# Sheet4.net
KiCad netlist of a schematic drawn in Altium Designer
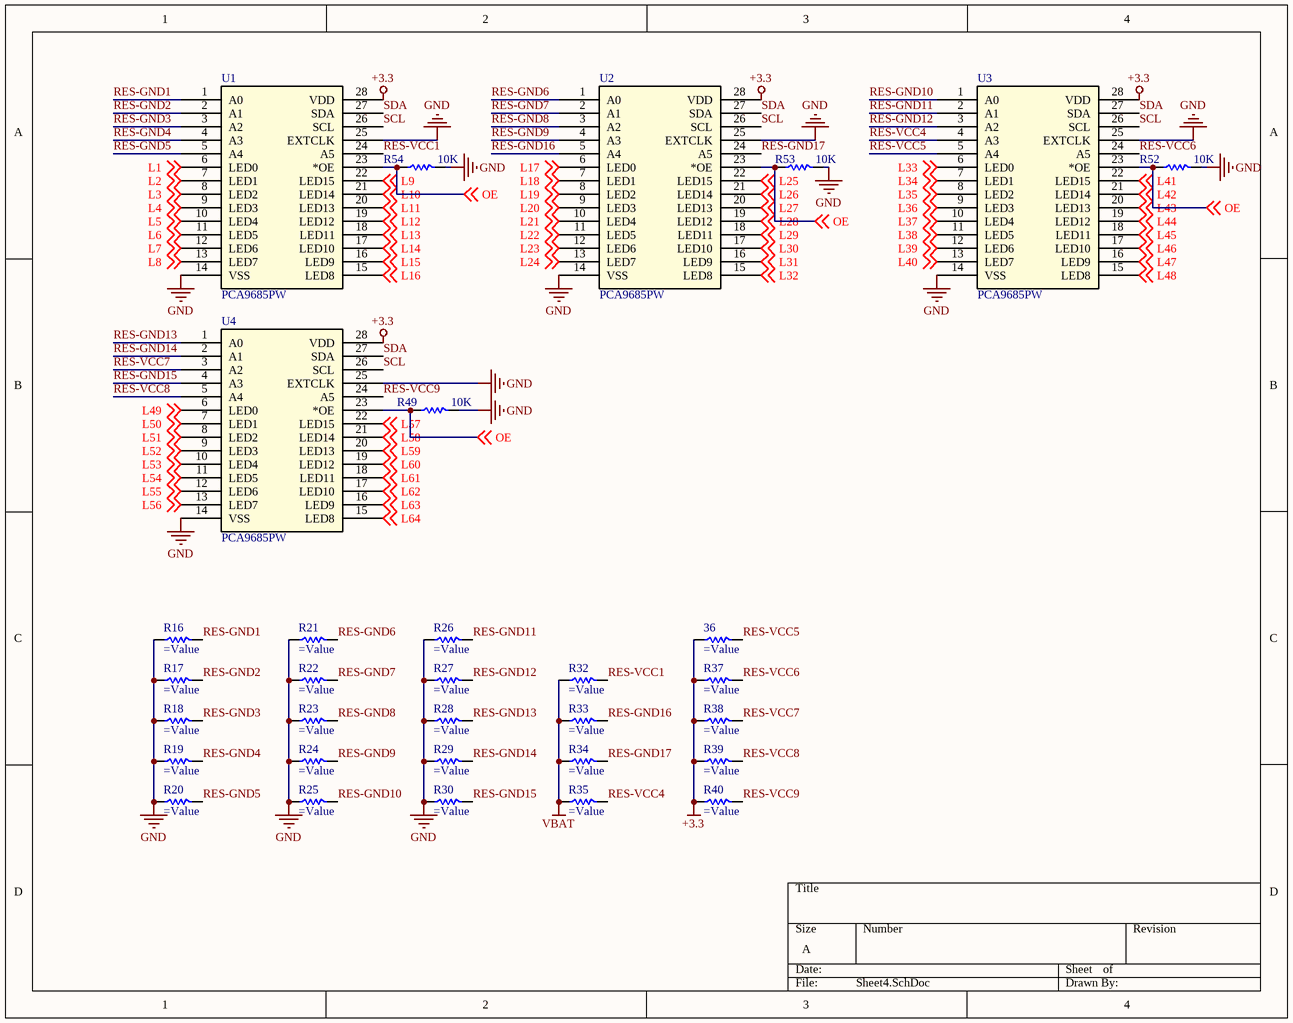
[diagram p0: Sheet4.SchDoc]

(export (version "E")
  (design (tool "Eeschema 10.0.6"))
  (components
    (comp (ref "36")
      (value "~")
      (footprint "R 0805")
      (description "Chip resistor")
      (fields (field (name "版权归属") "源创客"))
      (libsource (lib "Passive (Resistor-Capacitor-Inductor-Veristor-Ferrite)") (part "R"))
    )
    (comp (ref "R16")
      (value "~")
      (footprint "R 0805")
      (description "Chip resistor")
      (fields (field (name "版权归属") "源创客"))
      (libsource (lib "Passive (Resistor-Capacitor-Inductor-Veristor-Ferrite)") (part "R"))
    )
    (comp (ref "R17")
      (value "~")
      (footprint "R 0805")
      (description "Chip resistor")
      (fields (field (name "版权归属") "源创客"))
      (libsource (lib "Passive (Resistor-Capacitor-Inductor-Veristor-Ferrite)") (part "R"))
    )
    (comp (ref "R18")
      (value "~")
      (footprint "R 0805")
      (description "Chip resistor")
      (fields (field (name "版权归属") "源创客"))
      (libsource (lib "Passive (Resistor-Capacitor-Inductor-Veristor-Ferrite)") (part "R"))
    )
    (comp (ref "R19")
      (value "~")
      (footprint "R 0805")
      (description "Chip resistor")
      (fields (field (name "版权归属") "源创客"))
      (libsource (lib "Passive (Resistor-Capacitor-Inductor-Veristor-Ferrite)") (part "R"))
    )
    (comp (ref "R20")
      (value "~")
      (footprint "R 0805")
      (description "Chip resistor")
      (fields (field (name "版权归属") "源创客"))
      (libsource (lib "Passive (Resistor-Capacitor-Inductor-Veristor-Ferrite)") (part "R"))
    )
    (comp (ref "R21")
      (value "~")
      (footprint "R 0805")
      (description "Chip resistor")
      (fields (field (name "版权归属") "源创客"))
      (libsource (lib "Passive (Resistor-Capacitor-Inductor-Veristor-Ferrite)") (part "R"))
    )
    (comp (ref "R22")
      (value "~")
      (footprint "R 0805")
      (description "Chip resistor")
      (fields (field (name "版权归属") "源创客"))
      (libsource (lib "Passive (Resistor-Capacitor-Inductor-Veristor-Ferrite)") (part "R"))
    )
    (comp (ref "R23")
      (value "~")
      (footprint "R 0805")
      (description "Chip resistor")
      (fields (field (name "版权归属") "源创客"))
      (libsource (lib "Passive (Resistor-Capacitor-Inductor-Veristor-Ferrite)") (part "R"))
    )
    (comp (ref "R24")
      (value "~")
      (footprint "R 0805")
      (description "Chip resistor")
      (fields (field (name "版权归属") "源创客"))
      (libsource (lib "Passive (Resistor-Capacitor-Inductor-Veristor-Ferrite)") (part "R"))
    )
    (comp (ref "R25")
      (value "~")
      (footprint "R 0805")
      (description "Chip resistor")
      (fields (field (name "版权归属") "源创客"))
      (libsource (lib "Passive (Resistor-Capacitor-Inductor-Veristor-Ferrite)") (part "R"))
    )
    (comp (ref "R26")
      (value "~")
      (footprint "R 0805")
      (description "Chip resistor")
      (fields (field (name "版权归属") "源创客"))
      (libsource (lib "Passive (Resistor-Capacitor-Inductor-Veristor-Ferrite)") (part "R"))
    )
    (comp (ref "R27")
      (value "~")
      (footprint "R 0805")
      (description "Chip resistor")
      (fields (field (name "版权归属") "源创客"))
      (libsource (lib "Passive (Resistor-Capacitor-Inductor-Veristor-Ferrite)") (part "R"))
    )
    (comp (ref "R28")
      (value "~")
      (footprint "R 0805")
      (description "Chip resistor")
      (fields (field (name "版权归属") "源创客"))
      (libsource (lib "Passive (Resistor-Capacitor-Inductor-Veristor-Ferrite)") (part "R"))
    )
    (comp (ref "R29")
      (value "~")
      (footprint "R 0805")
      (description "Chip resistor")
      (fields (field (name "版权归属") "源创客"))
      (libsource (lib "Passive (Resistor-Capacitor-Inductor-Veristor-Ferrite)") (part "R"))
    )
    (comp (ref "R30")
      (value "~")
      (footprint "R 0805")
      (description "Chip resistor")
      (fields (field (name "版权归属") "源创客"))
      (libsource (lib "Passive (Resistor-Capacitor-Inductor-Veristor-Ferrite)") (part "R"))
    )
    (comp (ref "R32")
      (value "~")
      (footprint "R 0805")
      (description "Chip resistor")
      (fields (field (name "版权归属") "源创客"))
      (libsource (lib "Passive (Resistor-Capacitor-Inductor-Veristor-Ferrite)") (part "R"))
    )
    (comp (ref "R33")
      (value "~")
      (footprint "R 0805")
      (description "Chip resistor")
      (fields (field (name "版权归属") "源创客"))
      (libsource (lib "Passive (Resistor-Capacitor-Inductor-Veristor-Ferrite)") (part "R"))
    )
    (comp (ref "R34")
      (value "~")
      (footprint "R 0805")
      (description "Chip resistor")
      (fields (field (name "版权归属") "源创客"))
      (libsource (lib "Passive (Resistor-Capacitor-Inductor-Veristor-Ferrite)") (part "R"))
    )
    (comp (ref "R35")
      (value "~")
      (footprint "R 0805")
      (description "Chip resistor")
      (fields (field (name "版权归属") "源创客"))
      (libsource (lib "Passive (Resistor-Capacitor-Inductor-Veristor-Ferrite)") (part "R"))
    )
    (comp (ref "R37")
      (value "~")
      (footprint "R 0805")
      (description "Chip resistor")
      (fields (field (name "版权归属") "源创客"))
      (libsource (lib "Passive (Resistor-Capacitor-Inductor-Veristor-Ferrite)") (part "R"))
    )
    (comp (ref "R38")
      (value "~")
      (footprint "R 0805")
      (description "Chip resistor")
      (fields (field (name "版权归属") "源创客"))
      (libsource (lib "Passive (Resistor-Capacitor-Inductor-Veristor-Ferrite)") (part "R"))
    )
    (comp (ref "R39")
      (value "~")
      (footprint "R 0805")
      (description "Chip resistor")
      (fields (field (name "版权归属") "源创客"))
      (libsource (lib "Passive (Resistor-Capacitor-Inductor-Veristor-Ferrite)") (part "R"))
    )
    (comp (ref "R40")
      (value "~")
      (footprint "R 0805")
      (description "Chip resistor")
      (fields (field (name "版权归属") "源创客"))
      (libsource (lib "Passive (Resistor-Capacitor-Inductor-Veristor-Ferrite)") (part "R"))
    )
    (comp (ref "R49")
      (value "10K")
      (footprint "R 0805")
      (description "Chip resistor")
      (fields (field (name "版权归属") "源创客"))
      (libsource (lib "Passive (Resistor-Capacitor-Inductor-Veristor-Ferrite)") (part "R"))
    )
    (comp (ref "R52")
      (value "10K")
      (footprint "R 0805")
      (description "Chip resistor")
      (fields (field (name "版权归属") "源创客"))
      (libsource (lib "Passive (Resistor-Capacitor-Inductor-Veristor-Ferrite)") (part "R"))
    )
    (comp (ref "R53")
      (value "10K")
      (footprint "R 0805")
      (description "Chip resistor")
      (fields (field (name "版权归属") "源创客"))
      (libsource (lib "Passive (Resistor-Capacitor-Inductor-Veristor-Ferrite)") (part "R"))
    )
    (comp (ref "R54")
      (value "10K")
      (footprint "R 0805")
      (description "Chip resistor")
      (fields (field (name "版权归属") "源创客"))
      (libsource (lib "Passive (Resistor-Capacitor-Inductor-Veristor-Ferrite)") (part "R"))
    )
    (comp (ref "U1")
      (value "PCA9685PW")
      (footprint "SOT361-1_NXP")
      (description "No Description Available")
      (fields (field (name "COPYRIGHT") "Copyright (C) 2018 Accelerated Designs. All rights reserved"))
      (libsource (lib "PCA9685") (part "PCA9685PW"))
    )
    (comp (ref "U2")
      (value "PCA9685PW")
      (footprint "SOT361-1_NXP")
      (description "No Description Available")
      (fields (field (name "COPYRIGHT") "Copyright (C) 2018 Accelerated Designs. All rights reserved"))
      (libsource (lib "PCA9685") (part "PCA9685PW"))
    )
    (comp (ref "U3")
      (value "PCA9685PW")
      (footprint "SOT361-1_NXP")
      (description "No Description Available")
      (fields (field (name "COPYRIGHT") "Copyright (C) 2018 Accelerated Designs. All rights reserved"))
      (libsource (lib "PCA9685") (part "PCA9685PW"))
    )
    (comp (ref "U4")
      (value "PCA9685PW")
      (footprint "SOT361-1_NXP")
      (description "No Description Available")
      (fields (field (name "COPYRIGHT") "Copyright (C) 2018 Accelerated Designs. All rights reserved"))
      (libsource (lib "PCA9685") (part "PCA9685PW"))
    )
  )
  (nets
    (net (code "1") (name "+3.3") (class "Default")
      (node (ref "36") (pin "1") (pinfunction "1_1") (pintype "passive"))
      (node (ref "R37") (pin "1") (pinfunction "1_1") (pintype "passive"))
      (node (ref "R38") (pin "1") (pinfunction "1_1") (pintype "passive"))
      (node (ref "R39") (pin "1") (pinfunction "1_1") (pintype "passive"))
      (node (ref "R40") (pin "1") (pinfunction "1_1") (pintype "passive"))
      (node (ref "U1") (pin "28") (pinfunction "VDD_28") (pintype "passive"))
      (node (ref "U2") (pin "28") (pinfunction "VDD_28") (pintype "passive"))
      (node (ref "U3") (pin "28") (pinfunction "VDD_28") (pintype "passive"))
      (node (ref "U4") (pin "28") (pinfunction "VDD_28") (pintype "passive"))
    )
    (net (code "2") (name "/RES-GND1") (class "Default")
      (node (ref "R16") (pin "2") (pinfunction "2_2") (pintype "passive"))
      (node (ref "U1") (pin "1") (pinfunction "A0_1") (pintype "passive"))
    )
    (net (code "3") (name "/RES-GND2") (class "Default")
      (node (ref "R17") (pin "2") (pinfunction "2_2") (pintype "passive"))
      (node (ref "U1") (pin "2") (pinfunction "A1_2") (pintype "passive"))
    )
    (net (code "4") (name "/RES-GND3") (class "Default")
      (node (ref "R18") (pin "2") (pinfunction "2_2") (pintype "passive"))
      (node (ref "U1") (pin "3") (pinfunction "A2_3") (pintype "passive"))
    )
    (net (code "5") (name "/RES-GND4") (class "Default")
      (node (ref "R19") (pin "2") (pinfunction "2_2") (pintype "passive"))
      (node (ref "U1") (pin "4") (pinfunction "A3_4") (pintype "passive"))
    )
    (net (code "6") (name "/RES-GND5") (class "Default")
      (node (ref "R20") (pin "2") (pinfunction "2_2") (pintype "passive"))
      (node (ref "U1") (pin "5") (pinfunction "A4_5") (pintype "passive"))
    )
    (net (code "7") (name "/RES-GND6") (class "Default")
      (node (ref "R21") (pin "2") (pinfunction "2_2") (pintype "passive"))
      (node (ref "U2") (pin "1") (pinfunction "A0_1") (pintype "passive"))
    )
    (net (code "8") (name "/RES-GND7") (class "Default")
      (node (ref "R22") (pin "2") (pinfunction "2_2") (pintype "passive"))
      (node (ref "U2") (pin "2") (pinfunction "A1_2") (pintype "passive"))
    )
    (net (code "9") (name "/RES-GND8") (class "Default")
      (node (ref "R23") (pin "2") (pinfunction "2_2") (pintype "passive"))
      (node (ref "U2") (pin "3") (pinfunction "A2_3") (pintype "passive"))
    )
    (net (code "10") (name "/RES-GND9") (class "Default")
      (node (ref "R24") (pin "2") (pinfunction "2_2") (pintype "passive"))
      (node (ref "U2") (pin "4") (pinfunction "A3_4") (pintype "passive"))
    )
    (net (code "11") (name "/RES-GND10") (class "Default")
      (node (ref "R25") (pin "2") (pinfunction "2_2") (pintype "passive"))
      (node (ref "U3") (pin "1") (pinfunction "A0_1") (pintype "passive"))
    )
    (net (code "12") (name "/RES-GND11") (class "Default")
      (node (ref "R26") (pin "2") (pinfunction "2_2") (pintype "passive"))
      (node (ref "U3") (pin "2") (pinfunction "A1_2") (pintype "passive"))
    )
    (net (code "13") (name "/RES-GND12") (class "Default")
      (node (ref "R27") (pin "2") (pinfunction "2_2") (pintype "passive"))
      (node (ref "U3") (pin "3") (pinfunction "A2_3") (pintype "passive"))
    )
    (net (code "14") (name "/RES-GND13") (class "Default")
      (node (ref "R28") (pin "2") (pinfunction "2_2") (pintype "passive"))
      (node (ref "U4") (pin "1") (pinfunction "A0_1") (pintype "passive"))
    )
    (net (code "15") (name "/RES-GND14") (class "Default")
      (node (ref "R29") (pin "2") (pinfunction "2_2") (pintype "passive"))
      (node (ref "U4") (pin "2") (pinfunction "A1_2") (pintype "passive"))
    )
    (net (code "16") (name "/RES-GND15") (class "Default")
      (node (ref "R30") (pin "2") (pinfunction "2_2") (pintype "passive"))
      (node (ref "U4") (pin "4") (pinfunction "A3_4") (pintype "passive"))
    )
    (net (code "17") (name "/RES-GND16") (class "Default")
      (node (ref "R33") (pin "2") (pinfunction "2_2") (pintype "passive"))
      (node (ref "U2") (pin "5") (pinfunction "A4_5") (pintype "passive"))
    )
    (net (code "18") (name "/RES-GND17") (class "Default")
      (node (ref "R34") (pin "2") (pinfunction "2_2") (pintype "passive"))
      (node (ref "U2") (pin "24") (pinfunction "A5_24") (pintype "passive"))
    )
    (net (code "19") (name "/RES-VCC1") (class "Default")
      (node (ref "R32") (pin "2") (pinfunction "2_2") (pintype "passive"))
      (node (ref "U1") (pin "24") (pinfunction "A5_24") (pintype "passive"))
    )
    (net (code "20") (name "/RES-VCC4") (class "Default")
      (node (ref "R35") (pin "2") (pinfunction "2_2") (pintype "passive"))
      (node (ref "U3") (pin "4") (pinfunction "A3_4") (pintype "passive"))
    )
    (net (code "21") (name "/RES-VCC5") (class "Default")
      (node (ref "36") (pin "2") (pinfunction "2_2") (pintype "passive"))
      (node (ref "U3") (pin "5") (pinfunction "A4_5") (pintype "passive"))
    )
    (net (code "22") (name "/RES-VCC6") (class "Default")
      (node (ref "R37") (pin "2") (pinfunction "2_2") (pintype "passive"))
      (node (ref "U3") (pin "24") (pinfunction "A5_24") (pintype "passive"))
    )
    (net (code "23") (name "/RES-VCC7") (class "Default")
      (node (ref "R38") (pin "2") (pinfunction "2_2") (pintype "passive"))
      (node (ref "U4") (pin "3") (pinfunction "A2_3") (pintype "passive"))
    )
    (net (code "24") (name "/RES-VCC8") (class "Default")
      (node (ref "R39") (pin "2") (pinfunction "2_2") (pintype "passive"))
      (node (ref "U4") (pin "5") (pinfunction "A4_5") (pintype "passive"))
    )
    (net (code "25") (name "/RES-VCC9") (class "Default")
      (node (ref "R40") (pin "2") (pinfunction "2_2") (pintype "passive"))
      (node (ref "U4") (pin "24") (pinfunction "A5_24") (pintype "passive"))
    )
    (net (code "26") (name "/SCL") (class "Default")
      (node (ref "U1") (pin "26") (pinfunction "SCL_26") (pintype "passive"))
      (node (ref "U2") (pin "26") (pinfunction "SCL_26") (pintype "passive"))
      (node (ref "U3") (pin "26") (pinfunction "SCL_26") (pintype "passive"))
      (node (ref "U4") (pin "26") (pinfunction "SCL_26") (pintype "passive"))
    )
    (net (code "27") (name "/SDA") (class "Default")
      (node (ref "U1") (pin "27") (pinfunction "SDA_27") (pintype "passive"))
      (node (ref "U2") (pin "27") (pinfunction "SDA_27") (pintype "passive"))
      (node (ref "U3") (pin "27") (pinfunction "SDA_27") (pintype "passive"))
      (node (ref "U4") (pin "27") (pinfunction "SDA_27") (pintype "passive"))
    )
    (net (code "28") (name "GND") (class "Default")
      (node (ref "R16") (pin "1") (pinfunction "1_1") (pintype "passive"))
      (node (ref "R17") (pin "1") (pinfunction "1_1") (pintype "passive"))
      (node (ref "R18") (pin "1") (pinfunction "1_1") (pintype "passive"))
      (node (ref "R19") (pin "1") (pinfunction "1_1") (pintype "passive"))
      (node (ref "R20") (pin "1") (pinfunction "1_1") (pintype "passive"))
      (node (ref "R21") (pin "1") (pinfunction "1_1") (pintype "passive"))
      (node (ref "R22") (pin "1") (pinfunction "1_1") (pintype "passive"))
      (node (ref "R23") (pin "1") (pinfunction "1_1") (pintype "passive"))
      (node (ref "R24") (pin "1") (pinfunction "1_1") (pintype "passive"))
      (node (ref "R25") (pin "1") (pinfunction "1_1") (pintype "passive"))
      (node (ref "R26") (pin "1") (pinfunction "1_1") (pintype "passive"))
      (node (ref "R27") (pin "1") (pinfunction "1_1") (pintype "passive"))
      (node (ref "R28") (pin "1") (pinfunction "1_1") (pintype "passive"))
      (node (ref "R29") (pin "1") (pinfunction "1_1") (pintype "passive"))
      (node (ref "R30") (pin "1") (pinfunction "1_1") (pintype "passive"))
      (node (ref "R49") (pin "2") (pinfunction "2_2") (pintype "passive"))
      (node (ref "R52") (pin "2") (pinfunction "2_2") (pintype "passive"))
      (node (ref "R53") (pin "2") (pinfunction "2_2") (pintype "passive"))
      (node (ref "R54") (pin "2") (pinfunction "2_2") (pintype "passive"))
      (node (ref "U1") (pin "14") (pinfunction "VSS_14") (pintype "passive"))
      (node (ref "U1") (pin "25") (pinfunction "EXTCLK_25") (pintype "passive"))
      (node (ref "U2") (pin "14") (pinfunction "VSS_14") (pintype "passive"))
      (node (ref "U2") (pin "25") (pinfunction "EXTCLK_25") (pintype "passive"))
      (node (ref "U3") (pin "14") (pinfunction "VSS_14") (pintype "passive"))
      (node (ref "U3") (pin "25") (pinfunction "EXTCLK_25") (pintype "passive"))
      (node (ref "U4") (pin "14") (pinfunction "VSS_14") (pintype "passive"))
      (node (ref "U4") (pin "25") (pinfunction "EXTCLK_25") (pintype "passive"))
    )
    (net (code "29") (name "L1") (class "Default")
      (node (ref "U1") (pin "6") (pinfunction "LED0_6") (pintype "passive"))
    )
    (net (code "30") (name "L2") (class "Default")
      (node (ref "U1") (pin "7") (pinfunction "LED1_7") (pintype "passive"))
    )
    (net (code "31") (name "L3") (class "Default")
      (node (ref "U1") (pin "8") (pinfunction "LED2_8") (pintype "passive"))
    )
    (net (code "32") (name "L4") (class "Default")
      (node (ref "U1") (pin "9") (pinfunction "LED3_9") (pintype "passive"))
    )
    (net (code "33") (name "L5") (class "Default")
      (node (ref "U1") (pin "10") (pinfunction "LED4_10") (pintype "passive"))
    )
    (net (code "34") (name "L6") (class "Default")
      (node (ref "U1") (pin "11") (pinfunction "LED5_11") (pintype "passive"))
    )
    (net (code "35") (name "L7") (class "Default")
      (node (ref "U1") (pin "12") (pinfunction "LED6_12") (pintype "passive"))
    )
    (net (code "36") (name "L8") (class "Default")
      (node (ref "U1") (pin "13") (pinfunction "LED7_13") (pintype "passive"))
    )
    (net (code "37") (name "L9") (class "Default")
      (node (ref "U1") (pin "22") (pinfunction "LED15_22") (pintype "passive"))
    )
    (net (code "38") (name "L10") (class "Default")
      (node (ref "U1") (pin "21") (pinfunction "LED14_21") (pintype "passive"))
    )
    (net (code "39") (name "L11") (class "Default")
      (node (ref "U1") (pin "20") (pinfunction "LED13_20") (pintype "passive"))
    )
    (net (code "40") (name "L12") (class "Default")
      (node (ref "U1") (pin "19") (pinfunction "LED12_19") (pintype "passive"))
    )
    (net (code "41") (name "L13") (class "Default")
      (node (ref "U1") (pin "18") (pinfunction "LED11_18") (pintype "passive"))
    )
    (net (code "42") (name "L14") (class "Default")
      (node (ref "U1") (pin "17") (pinfunction "LED10_17") (pintype "passive"))
    )
    (net (code "43") (name "L15") (class "Default")
      (node (ref "U1") (pin "16") (pinfunction "LED9_16") (pintype "passive"))
    )
    (net (code "44") (name "L16") (class "Default")
      (node (ref "U1") (pin "15") (pinfunction "LED8_15") (pintype "passive"))
    )
    (net (code "45") (name "L17") (class "Default")
      (node (ref "U2") (pin "6") (pinfunction "LED0_6") (pintype "passive"))
    )
    (net (code "46") (name "L18") (class "Default")
      (node (ref "U2") (pin "7") (pinfunction "LED1_7") (pintype "passive"))
    )
    (net (code "47") (name "L19") (class "Default")
      (node (ref "U2") (pin "8") (pinfunction "LED2_8") (pintype "passive"))
    )
    (net (code "48") (name "L20") (class "Default")
      (node (ref "U2") (pin "9") (pinfunction "LED3_9") (pintype "passive"))
    )
    (net (code "49") (name "L21") (class "Default")
      (node (ref "U2") (pin "10") (pinfunction "LED4_10") (pintype "passive"))
    )
    (net (code "50") (name "L22") (class "Default")
      (node (ref "U2") (pin "11") (pinfunction "LED5_11") (pintype "passive"))
    )
    (net (code "51") (name "L23") (class "Default")
      (node (ref "U2") (pin "12") (pinfunction "LED6_12") (pintype "passive"))
    )
    (net (code "52") (name "L24") (class "Default")
      (node (ref "U2") (pin "13") (pinfunction "LED7_13") (pintype "passive"))
    )
    (net (code "53") (name "L25") (class "Default")
      (node (ref "U2") (pin "22") (pinfunction "LED15_22") (pintype "passive"))
    )
    (net (code "54") (name "L26") (class "Default")
      (node (ref "U2") (pin "21") (pinfunction "LED14_21") (pintype "passive"))
    )
    (net (code "55") (name "L27") (class "Default")
      (node (ref "U2") (pin "20") (pinfunction "LED13_20") (pintype "passive"))
    )
    (net (code "56") (name "L28") (class "Default")
      (node (ref "U2") (pin "19") (pinfunction "LED12_19") (pintype "passive"))
    )
    (net (code "57") (name "L29") (class "Default")
      (node (ref "U2") (pin "18") (pinfunction "LED11_18") (pintype "passive"))
    )
    (net (code "58") (name "L30") (class "Default")
      (node (ref "U2") (pin "17") (pinfunction "LED10_17") (pintype "passive"))
    )
    (net (code "59") (name "L31") (class "Default")
      (node (ref "U2") (pin "16") (pinfunction "LED9_16") (pintype "passive"))
    )
    (net (code "60") (name "L32") (class "Default")
      (node (ref "U2") (pin "15") (pinfunction "LED8_15") (pintype "passive"))
    )
    (net (code "61") (name "L33") (class "Default")
      (node (ref "U3") (pin "6") (pinfunction "LED0_6") (pintype "passive"))
    )
    (net (code "62") (name "L34") (class "Default")
      (node (ref "U3") (pin "7") (pinfunction "LED1_7") (pintype "passive"))
    )
    (net (code "63") (name "L35") (class "Default")
      (node (ref "U3") (pin "8") (pinfunction "LED2_8") (pintype "passive"))
    )
    (net (code "64") (name "L36") (class "Default")
      (node (ref "U3") (pin "9") (pinfunction "LED3_9") (pintype "passive"))
    )
    (net (code "65") (name "L37") (class "Default")
      (node (ref "U3") (pin "10") (pinfunction "LED4_10") (pintype "passive"))
    )
    (net (code "66") (name "L38") (class "Default")
      (node (ref "U3") (pin "11") (pinfunction "LED5_11") (pintype "passive"))
    )
    (net (code "67") (name "L39") (class "Default")
      (node (ref "U3") (pin "12") (pinfunction "LED6_12") (pintype "passive"))
    )
    (net (code "68") (name "L40") (class "Default")
      (node (ref "U3") (pin "13") (pinfunction "LED7_13") (pintype "passive"))
    )
    (net (code "69") (name "L41") (class "Default")
      (node (ref "U3") (pin "22") (pinfunction "LED15_22") (pintype "passive"))
    )
    (net (code "70") (name "L42") (class "Default")
      (node (ref "U3") (pin "21") (pinfunction "LED14_21") (pintype "passive"))
    )
    (net (code "71") (name "L43") (class "Default")
      (node (ref "U3") (pin "20") (pinfunction "LED13_20") (pintype "passive"))
    )
    (net (code "72") (name "L44") (class "Default")
      (node (ref "U3") (pin "19") (pinfunction "LED12_19") (pintype "passive"))
    )
    (net (code "73") (name "L45") (class "Default")
      (node (ref "U3") (pin "18") (pinfunction "LED11_18") (pintype "passive"))
    )
    (net (code "74") (name "L46") (class "Default")
      (node (ref "U3") (pin "17") (pinfunction "LED10_17") (pintype "passive"))
    )
    (net (code "75") (name "L47") (class "Default")
      (node (ref "U3") (pin "16") (pinfunction "LED9_16") (pintype "passive"))
    )
    (net (code "76") (name "L48") (class "Default")
      (node (ref "U3") (pin "15") (pinfunction "LED8_15") (pintype "passive"))
    )
    (net (code "77") (name "L49") (class "Default")
      (node (ref "U4") (pin "6") (pinfunction "LED0_6") (pintype "passive"))
    )
    (net (code "78") (name "L50") (class "Default")
      (node (ref "U4") (pin "7") (pinfunction "LED1_7") (pintype "passive"))
    )
    (net (code "79") (name "L51") (class "Default")
      (node (ref "U4") (pin "8") (pinfunction "LED2_8") (pintype "passive"))
    )
    (net (code "80") (name "L52") (class "Default")
      (node (ref "U4") (pin "9") (pinfunction "LED3_9") (pintype "passive"))
    )
    (net (code "81") (name "L53") (class "Default")
      (node (ref "U4") (pin "10") (pinfunction "LED4_10") (pintype "passive"))
    )
    (net (code "82") (name "L54") (class "Default")
      (node (ref "U4") (pin "11") (pinfunction "LED5_11") (pintype "passive"))
    )
    (net (code "83") (name "L55") (class "Default")
      (node (ref "U4") (pin "12") (pinfunction "LED6_12") (pintype "passive"))
    )
    (net (code "84") (name "L56") (class "Default")
      (node (ref "U4") (pin "13") (pinfunction "LED7_13") (pintype "passive"))
    )
    (net (code "85") (name "L57") (class "Default")
      (node (ref "U4") (pin "22") (pinfunction "LED15_22") (pintype "passive"))
    )
    (net (code "86") (name "L58") (class "Default")
      (node (ref "U4") (pin "21") (pinfunction "LED14_21") (pintype "passive"))
    )
    (net (code "87") (name "L59") (class "Default")
      (node (ref "U4") (pin "20") (pinfunction "LED13_20") (pintype "passive"))
    )
    (net (code "88") (name "L60") (class "Default")
      (node (ref "U4") (pin "19") (pinfunction "LED12_19") (pintype "passive"))
    )
    (net (code "89") (name "L61") (class "Default")
      (node (ref "U4") (pin "18") (pinfunction "LED11_18") (pintype "passive"))
    )
    (net (code "90") (name "L62") (class "Default")
      (node (ref "U4") (pin "17") (pinfunction "LED10_17") (pintype "passive"))
    )
    (net (code "91") (name "L63") (class "Default")
      (node (ref "U4") (pin "16") (pinfunction "LED9_16") (pintype "passive"))
    )
    (net (code "92") (name "L64") (class "Default")
      (node (ref "U4") (pin "15") (pinfunction "LED8_15") (pintype "passive"))
    )
    (net (code "93") (name "OE") (class "Default")
      (node (ref "R49") (pin "1") (pinfunction "1_1") (pintype "passive"))
      (node (ref "R52") (pin "1") (pinfunction "1_1") (pintype "passive"))
      (node (ref "R53") (pin "1") (pinfunction "1_1") (pintype "passive"))
      (node (ref "R54") (pin "1") (pinfunction "1_1") (pintype "passive"))
      (node (ref "U1") (pin "23") (pinfunction "*OE_23") (pintype "passive"))
      (node (ref "U2") (pin "23") (pinfunction "*OE_23") (pintype "passive"))
      (node (ref "U3") (pin "23") (pinfunction "*OE_23") (pintype "passive"))
      (node (ref "U4") (pin "23") (pinfunction "*OE_23") (pintype "passive"))
    )
    (net (code "94") (name "VBAT") (class "Default")
      (node (ref "R32") (pin "1") (pinfunction "1_1") (pintype "passive"))
      (node (ref "R33") (pin "1") (pinfunction "1_1") (pintype "passive"))
      (node (ref "R34") (pin "1") (pinfunction "1_1") (pintype "passive"))
      (node (ref "R35") (pin "1") (pinfunction "1_1") (pintype "passive"))
    )
  )
)
